# Voltage_Regulator.net
KiCad netlist of a schematic drawn in EAGLE
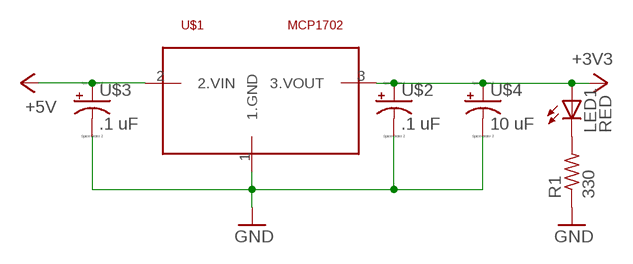
[diagram p0: schematic, sheet 1]

(export (version "E")
  (design (tool "Eeschema 10.0.6"))
  (components
    (comp (ref "LED1")
      (value "RED")
      (footprint "eagle-import:LED3MM")
      (libsource (lib "eagle-import") (part "LED3MM"))
    )
    (comp (ref "R1")
      (value "330")
      (footprint "eagle-import:0207_10")
      (libsource (lib "eagle-import") (part "R-US_0207/10"))
    )
    (comp (ref "U$1")
      (value "MCP1702")
      (footprint "eagle-import:TO92")
      (libsource (lib "eagle-import") (part "MCP1702"))
    )
    (comp (ref "U$2")
      (value ".1 uF")
      (footprint "eagle-import:E1,8-4")
      (libsource (lib "eagle-import") (part "CAP-4"))
    )
    (comp (ref "U$3")
      (value ".1 uF")
      (footprint "eagle-import:E1,8-4")
      (libsource (lib "eagle-import") (part "CAP-4"))
    )
    (comp (ref "U$4")
      (value "10 uF")
      (footprint "eagle-import:E2,5-5")
      (libsource (lib "eagle-import") (part "CAP-5"))
    )
  )
  (nets
    (net (code "1") (name "+3V3") (class "Default")
      (node (ref "LED1") (pin "A") (pinfunction "A_A") (pintype "passive"))
      (node (ref "U$1") (pin "3") (pinfunction "3.VOUT_3") (pintype "bidirectional"))
      (node (ref "U$2") (pin "+") (pinfunction "+_+") (pintype "passive"))
      (node (ref "U$4") (pin "+") (pinfunction "+_+") (pintype "passive"))
    )
    (net (code "2") (name "+5V") (class "Default")
      (node (ref "U$1") (pin "2") (pinfunction "2.VIN_2") (pintype "bidirectional"))
      (node (ref "U$3") (pin "+") (pinfunction "+_+") (pintype "passive"))
    )
    (net (code "3") (name "GND") (class "Default")
      (node (ref "R1") (pin "1") (pinfunction "1_1") (pintype "passive"))
      (node (ref "U$1") (pin "1") (pinfunction "1.GND_1") (pintype "bidirectional"))
      (node (ref "U$2") (pin "-") (pinfunction "-_-") (pintype "passive"))
      (node (ref "U$3") (pin "-") (pinfunction "-_-") (pintype "passive"))
      (node (ref "U$4") (pin "-") (pinfunction "-_-") (pintype "passive"))
    )
    (net (code "4") (name "Net-(LED1-C)") (class "Default")
      (node (ref "LED1") (pin "K") (pinfunction "C_K") (pintype "passive"))
      (node (ref "R1") (pin "2") (pinfunction "2_2") (pintype "passive"))
    )
  )
)
